# Battery_capacity_meter_board.net
KiCad netlist of a schematic drawn in Altium Designer
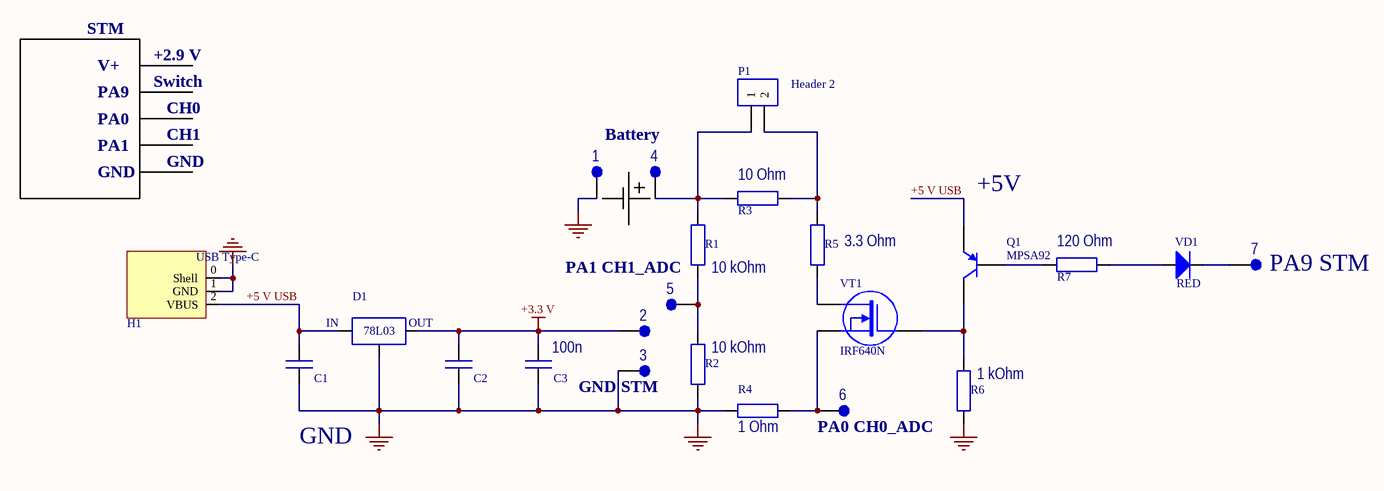
[diagram p0: Battery capacity meter_board.SchDoc]

(export (version "E")
  (design (tool "Eeschema 10.0.6"))
  (components
    (comp (ref "1")
      (value ".")
      (footprint "Battery capacity meter_board:Hole")
      (fields (field (name "PART NUMBER") "КТ_DIP_1,1"))
      (libsource (lib "Battery capacity meter_board") (part "KT"))
    )
    (comp (ref "2")
      (value ".")
      (footprint "Battery capacity meter_board:Hole")
      (fields (field (name "PART NUMBER") "КТ_DIP_1,1"))
      (libsource (lib "Battery capacity meter_board") (part "KT"))
    )
    (comp (ref "3")
      (value ".")
      (footprint "Battery capacity meter_board:Hole")
      (fields (field (name "PART NUMBER") "КТ_DIP_1,1"))
      (libsource (lib "Battery capacity meter_board") (part "KT"))
    )
    (comp (ref "4")
      (value ".")
      (footprint "Battery capacity meter_board:Hole")
      (fields (field (name "PART NUMBER") "КТ_DIP_1,1"))
      (libsource (lib "Battery capacity meter_board") (part "KT"))
    )
    (comp (ref "5")
      (value ".")
      (footprint "Battery capacity meter_board:Hole")
      (fields (field (name "PART NUMBER") "КТ_DIP_1,1"))
      (libsource (lib "Battery capacity meter_board") (part "KT"))
    )
    (comp (ref "6")
      (value ".")
      (footprint "Battery capacity meter_board:Hole")
      (fields (field (name "PART NUMBER") "КТ_DIP_1,1"))
      (libsource (lib "Battery capacity meter_board") (part "KT"))
    )
    (comp (ref "7")
      (value ".")
      (footprint "Battery capacity meter_board:Hole")
      (fields (field (name "PART NUMBER") "КТ_DIP_1,1"))
      (libsource (lib "Battery capacity meter_board") (part "KT"))
    )
    (comp (ref "C1")
      (value "Capacitor")
      (footprint "Battery capacity meter_board:C1206")
      (libsource (lib "1") (part "Capacitor"))
    )
    (comp (ref "C2")
      (value "Capacitor")
      (footprint "Battery capacity meter_board:C1206")
      (libsource (lib "1") (part "Capacitor"))
    )
    (comp (ref "C3")
      (value "Capacitor")
      (footprint "Battery capacity meter_board:C1206")
      (libsource (lib "1") (part "Capacitor"))
    )
    (comp (ref "D1")
      (value "78L03")
      (footprint "SOT89M")
      (fields (field (name "PUBLISHER") "Altium Limited"))
      (libsource (lib "1") (part "78L03"))
    )
    (comp (ref "H1")
      (value "USB Type-C")
      (footprint "Battery capacity meter_board:USB Type-C")
      (libsource (lib "Battery capacity meter_board") (part "USB Type-C"))
    )
    (comp (ref "P1")
      (value "Header 2")
      (footprint "Battery capacity meter_board:2pin")
      (description "Header, 2-Pin")
      (fields (field (name "PUBLISHER") "Altium Limited"))
      (libsource (lib "1") (part "Header 2"))
    )
    (comp (ref "Q1")
      (value "MPSA92")
      (footprint "Battery capacity meter_board:NPN")
      (description "PNP")
      (libsource (lib "Battery capacity meter_board") (part "MPSA92"))
    )
    (comp (ref "R1")
      (value "Rezistor_10k")
      (footprint "Battery capacity meter_board:2512")
      (description "Rezistor")
      (libsource (lib "Battery capacity meter_board") (part "Rezistor_10k"))
    )
    (comp (ref "R2")
      (value "Rezistor_10k")
      (footprint "Battery capacity meter_board:2512")
      (description "Rezistor")
      (libsource (lib "Battery capacity meter_board") (part "Rezistor_10k"))
    )
    (comp (ref "R3")
      (value "Rezistor_Ceramic_20W")
      (footprint "Battery capacity meter_board:Resistor_Ceramic_20W")
      (libsource (lib "Battery capacity meter_board") (part "Rezistor_Ceramic_20W"))
    )
    (comp (ref "R4")
      (value "Rezistor_Ceramic_20W")
      (footprint "Battery capacity meter_board:Resistor_Ceramic_20W")
      (libsource (lib "Battery capacity meter_board") (part "Rezistor_Ceramic_20W"))
    )
    (comp (ref "R5")
      (value "Rezistor_Ceramic_20W")
      (footprint "Battery capacity meter_board:Resistor_Ceramic_20W")
      (libsource (lib "") (part "Rezistor_Ceramic_20W_1"))
    )
    (comp (ref "R6")
      (value "Rezistor_10k")
      (footprint "Battery capacity meter_board:2512")
      (description "Rezistor")
      (libsource (lib "Battery capacity meter_board") (part "Rezistor_10k"))
    )
    (comp (ref "R7")
      (value "Rezistor_120")
      (footprint "Battery capacity meter_board:for 120 Ohm")
      (description "Rezistor")
      (libsource (lib "Battery capacity meter_board") (part "Rezistor_120"))
    )
    (comp (ref "VD1")
      (value "RED")
      (footprint "Battery capacity meter_board:Light_Diode")
      (libsource (lib "Battery capacity meter_board") (part "HER106"))
    )
    (comp (ref "VT1")
      (value "IRF640N")
      (footprint "Battery capacity meter_board:TO-220AB")
      (libsource (lib "Battery capacity meter_board") (part "IRF740"))
    )
  )
  (nets
    (net (code "1") (name "+3.3 V") (class "Default")
      (node (ref "2") (pin "1") (pinfunction "1_1") (pintype "passive"))
      (node (ref "C2") (pin "2") (pinfunction "2_2") (pintype "passive"))
      (node (ref "C3") (pin "2") (pinfunction "2_2") (pintype "passive"))
      (node (ref "D1") (pin "1") (pinfunction "1_1") (pintype "passive"))
    )
    (net (code "2") (name "/+5 V USB") (class "Default")
      (node (ref "C1") (pin "2") (pinfunction "2_2") (pintype "passive"))
      (node (ref "D1") (pin "3") (pinfunction "3_3") (pintype "passive"))
      (node (ref "H1") (pin "2") (pinfunction "VBUS_2") (pintype "passive"))
      (node (ref "Q1") (pin "1") (pinfunction "E_1") (pintype "passive"))
    )
    (net (code "3") (name "GND") (class "Default")
      (node (ref "1") (pin "1") (pinfunction "1_1") (pintype "passive"))
      (node (ref "3") (pin "1") (pinfunction "1_1") (pintype "passive"))
      (node (ref "C1") (pin "1") (pinfunction "1_1") (pintype "passive"))
      (node (ref "C2") (pin "1") (pinfunction "1_1") (pintype "passive"))
      (node (ref "C3") (pin "1") (pinfunction "1_1") (pintype "passive"))
      (node (ref "D1") (pin "2") (pinfunction "2_2") (pintype "passive"))
      (node (ref "H1") (pin "0") (pinfunction "Shell_0") (pintype "passive"))
      (node (ref "H1") (pin "1") (pinfunction "GND_1") (pintype "passive"))
      (node (ref "R2") (pin "1") (pinfunction "1_1") (pintype "passive"))
      (node (ref "R4") (pin "1") (pinfunction "1_1") (pintype "passive"))
      (node (ref "R6") (pin "1") (pinfunction "1_1") (pintype "passive"))
    )
    (net (code "4") (name "Net-(4-Pad1)") (class "Default")
      (node (ref "4") (pin "1") (pinfunction "1_1") (pintype "passive"))
      (node (ref "P1") (pin "1") (pinfunction "1_1") (pintype "passive"))
      (node (ref "R1") (pin "2") (pinfunction "2_2") (pintype "passive"))
      (node (ref "R3") (pin "1") (pinfunction "1_1") (pintype "passive"))
    )
    (net (code "5") (name "Net-(5-Pad1)") (class "Default")
      (node (ref "5") (pin "1") (pinfunction "1_1") (pintype "passive"))
      (node (ref "R1") (pin "1") (pinfunction "1_1") (pintype "passive"))
      (node (ref "R2") (pin "2") (pinfunction "2_2") (pintype "passive"))
    )
    (net (code "6") (name "Net-(P1-Pad2)") (class "Default")
      (node (ref "P1") (pin "2") (pinfunction "2_2") (pintype "passive"))
      (node (ref "R3") (pin "2") (pinfunction "2_2") (pintype "passive"))
      (node (ref "R5") (pin "2") (pinfunction "2_2") (pintype "passive"))
    )
    (net (code "7") (name "Net-(Q1-B)") (class "Default")
      (node (ref "Q1") (pin "3") (pinfunction "B_3") (pintype "passive"))
      (node (ref "R7") (pin "1") (pinfunction "1_1") (pintype "passive"))
    )
    (net (code "8") (name "Net-(Q1-C)") (class "Default")
      (node (ref "Q1") (pin "2") (pinfunction "C_2") (pintype "passive"))
      (node (ref "R6") (pin "2") (pinfunction "2_2") (pintype "passive"))
      (node (ref "VT1") (pin "1") (pinfunction "G_1") (pintype "passive"))
    )
    (net (code "9") (name "Net-(VD1-A)") (class "Default")
      (node (ref "R7") (pin "2") (pinfunction "2_2") (pintype "passive"))
      (node (ref "VD1") (pin "1") (pinfunction "A_1") (pintype "passive"))
    )
    (net (code "10") (name "Net-(VD1-K)") (class "Default")
      (node (ref "7") (pin "1") (pinfunction "1_1") (pintype "passive"))
      (node (ref "VD1") (pin "2") (pinfunction "K_2") (pintype "passive"))
    )
    (net (code "11") (name "Net-(VT1-D)") (class "Default")
      (node (ref "R5") (pin "1") (pinfunction "1_1") (pintype "passive"))
      (node (ref "VT1") (pin "2") (pinfunction "D_2") (pintype "passive"))
    )
    (net (code "12") (name "Net-(VT1-S)") (class "Default")
      (node (ref "6") (pin "1") (pinfunction "1_1") (pintype "passive"))
      (node (ref "R4") (pin "2") (pinfunction "2_2") (pintype "passive"))
      (node (ref "VT1") (pin "3") (pinfunction "S_3") (pintype "passive"))
    )
  )
)
